# REGULATOR_230.net
KiCad netlist of a schematic drawn in EAGLE
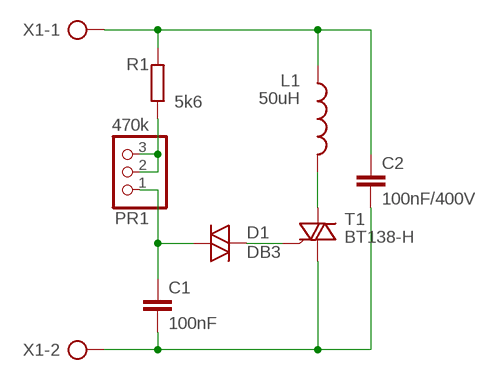
[diagram p0: schematic, sheet 1]

(export (version "E")
  (design (tool "Eeschema 10.0.6"))
  (components
    (comp (ref "C1")
      (value "100nF")
      (footprint "eagle-import:150-72-183")
      (libsource (lib "eagle-import") (part "C-EU"))
    )
    (comp (ref "C2")
      (value "100nF/400V")
      (footprint "eagle-import:150-72-183")
      (libsource (lib "eagle-import") (part "C-EU"))
    )
    (comp (ref "D1")
      (value "DB3")
      (footprint "eagle-import:DO-35-PION(3MM)")
      (libsource (lib "eagle-import") (part "DB3"))
    )
    (comp (ref "L1")
      (value "50uH")
      (footprint "eagle-import:C5-15")
      (libsource (lib "eagle-import") (part "L-US"))
    )
    (comp (ref "PR1")
      (value "470k")
      (footprint "eagle-import:1X03")
      (libsource (lib "eagle-import") (part "PINHD-1X3"))
    )
    (comp (ref "R1")
      (value "5k6")
      (footprint "eagle-import:204_7")
      (libsource (lib "eagle-import") (part "R-EU7"))
    )
    (comp (ref "T1")
      (value "BT138-H")
      (footprint "eagle-import:TO220BH")
      (libsource (lib "eagle-import") (part "BT138-H"))
    )
    (comp (ref "X1")
      (value "AK300/2")
      (footprint "eagle-import:AK300_2")
      (libsource (lib "eagle-import") (part "AK300/2"))
    )
  )
  (nets
    (net (code "1") (name "Net-(C1-1)") (class "Default")
      (node (ref "C1") (pin "P$1") (pinfunction "1_P$1") (pintype "passive"))
      (node (ref "D1") (pin "P$1") (pinfunction "1_P$1") (pintype "passive"))
      (node (ref "PR1") (pin "1") (pinfunction "1_1") (pintype "passive"))
    )
    (net (code "2") (name "Net-(C1-2)") (class "Default")
      (node (ref "C1") (pin "P$2") (pinfunction "2_P$2") (pintype "passive"))
      (node (ref "C2") (pin "P$2") (pinfunction "2_P$2") (pintype "passive"))
      (node (ref "T1") (pin "T1") (pinfunction "A1_T1") (pintype "passive"))
      (node (ref "X1") (pin "2") (pinfunction "KL_2") (pintype "passive"))
    )
    (net (code "3") (name "Net-(C2-1)") (class "Default")
      (node (ref "C2") (pin "P$1") (pinfunction "1_P$1") (pintype "passive"))
      (node (ref "L1") (pin "P$1") (pinfunction "1_P$1") (pintype "passive"))
      (node (ref "R1") (pin "P$2") (pinfunction "2_P$2") (pintype "passive"))
      (node (ref "X1") (pin "1") (pinfunction "KL_1") (pintype "passive"))
    )
    (net (code "4") (name "Net-(D1-2)") (class "Default")
      (node (ref "D1") (pin "P$2") (pinfunction "2_P$2") (pintype "passive"))
      (node (ref "T1") (pin "G") (pinfunction "G_G") (pintype "passive"))
    )
    (net (code "5") (name "Net-(L1-2)") (class "Default")
      (node (ref "L1") (pin "P$2") (pinfunction "2_P$2") (pintype "passive"))
      (node (ref "T1") (pin "T2") (pinfunction "A2_T2") (pintype "passive"))
    )
    (net (code "6") (name "Net-(R1-1)") (class "Default")
      (node (ref "PR1") (pin "2") (pinfunction "2_2") (pintype "passive"))
      (node (ref "PR1") (pin "3") (pinfunction "3_3") (pintype "passive"))
      (node (ref "R1") (pin "P$1") (pinfunction "1_P$1") (pintype "passive"))
    )
  )
)
